# Controller_v1.net
KiCad netlist of a schematic drawn in EAGLE
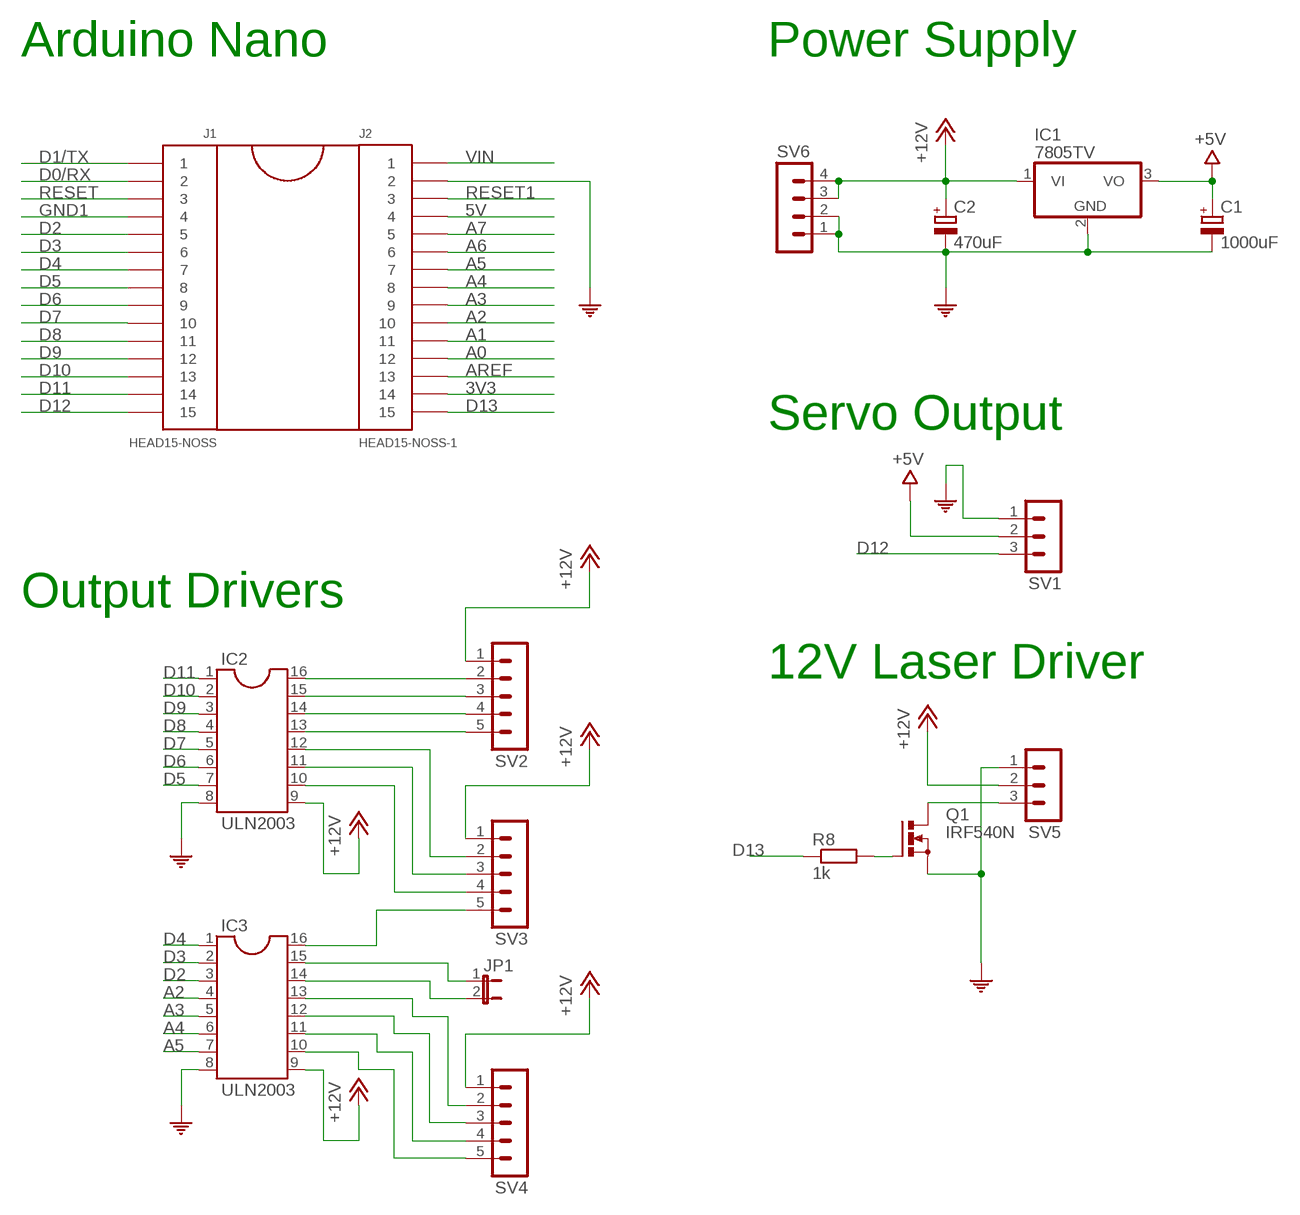
[diagram p0: schematic, sheet 1]

(export (version "E")
  (design (tool "Eeschema 10.0.6"))
  (components
    (comp (ref "C1")
      (value "1000uF")
      (footprint "eagle-import:TAP5-70")
      (libsource (lib "eagle-import") (part "CPOL-EUTAP5-70"))
    )
    (comp (ref "C2")
      (value "470uF")
      (footprint "eagle-import:TAP5-70")
      (libsource (lib "eagle-import") (part "CPOL-EUTAP5-70"))
    )
    (comp (ref "IC1")
      (value "7805TV")
      (footprint "eagle-import:TO220V")
      (libsource (lib "eagle-import") (part "78TV05"))
    )
    (comp (ref "IC2")
      (value "ULN2003")
      (footprint "eagle-import:DIL16")
      (libsource (lib "eagle-import") (part "DIL16"))
    )
    (comp (ref "IC3")
      (value "ULN2003")
      (footprint "eagle-import:DIL16")
      (libsource (lib "eagle-import") (part "DIL16"))
    )
    (comp (ref "J1")
      (value "HEAD15-NOSS")
      (footprint "eagle-import:HEAD15-NOSS")
      (libsource (lib "eagle-import") (part "HEAD15-NOSS"))
    )
    (comp (ref "J2")
      (value "HEAD15-NOSS-1")
      (footprint "eagle-import:HEAD15-NOSS-1")
      (libsource (lib "eagle-import") (part "HEAD15-NOSS-1"))
    )
    (comp (ref "JP1")
      (value "JP1E")
      (footprint "eagle-import:JP1")
      (libsource (lib "eagle-import") (part "JP1E"))
    )
    (comp (ref "Q1")
      (value "IRF540N")
      (footprint "eagle-import:TO220BV")
      (libsource (lib "eagle-import") (part "PMOSFET_NTO220BV"))
    )
    (comp (ref "R8")
      (value "1k")
      (footprint "eagle-import:0207_10")
      (libsource (lib "eagle-import") (part "R-EU_0207/10"))
    )
    (comp (ref "SV1")
      (value "MA03-1")
      (footprint "eagle-import:MA03-1")
      (libsource (lib "eagle-import") (part "MA03-1"))
    )
    (comp (ref "SV2")
      (value "MA05-1")
      (footprint "eagle-import:MA05-1")
      (libsource (lib "eagle-import") (part "MA05-1"))
    )
    (comp (ref "SV3")
      (value "MA05-1")
      (footprint "eagle-import:MA05-1")
      (libsource (lib "eagle-import") (part "MA05-1"))
    )
    (comp (ref "SV4")
      (value "MA05-1")
      (footprint "eagle-import:MA05-1")
      (libsource (lib "eagle-import") (part "MA05-1"))
    )
    (comp (ref "SV5")
      (value "MA03-1")
      (footprint "eagle-import:MA03-1")
      (libsource (lib "eagle-import") (part "MA03-1"))
    )
    (comp (ref "SV6")
      (value "MA04-1")
      (footprint "eagle-import:MA04-1")
      (libsource (lib "eagle-import") (part "MA04-1"))
    )
  )
  (nets
    (net (code "1") (name "+5V") (class "Default")
      (node (ref "C1") (pin "+") (pinfunction "+_+") (pintype "passive"))
      (node (ref "IC1") (pin "3") (pinfunction "VO_3") (pintype "passive"))
      (node (ref "SV1") (pin "2") (pinfunction "2_2") (pintype "passive"))
    )
    (net (code "2") (name "+12V") (class "Default")
      (node (ref "C2") (pin "+") (pinfunction "+_+") (pintype "passive"))
      (node (ref "IC1") (pin "1") (pinfunction "VI_1") (pintype "input"))
      (node (ref "IC2") (pin "9") (pinfunction "9_9") (pintype "passive"))
      (node (ref "IC3") (pin "9") (pinfunction "9_9") (pintype "passive"))
      (node (ref "SV2") (pin "1") (pinfunction "1_1") (pintype "passive"))
      (node (ref "SV3") (pin "1") (pinfunction "1_1") (pintype "passive"))
      (node (ref "SV4") (pin "1") (pinfunction "1_1") (pintype "passive"))
      (node (ref "SV5") (pin "2") (pinfunction "2_2") (pintype "passive"))
      (node (ref "SV6") (pin "3") (pinfunction "3_3") (pintype "passive"))
      (node (ref "SV6") (pin "4") (pinfunction "4_4") (pintype "passive"))
    )
    (net (code "3") (name "/3V3") (class "Default")
      (node (ref "J2") (pin "14") (pinfunction "14_14") (pintype "passive"))
    )
    (net (code "4") (name "/5V") (class "Default")
      (node (ref "J2") (pin "4") (pinfunction "4_4") (pintype "passive"))
    )
    (net (code "5") (name "/A0") (class "Default")
      (node (ref "J2") (pin "12") (pinfunction "12_12") (pintype "passive"))
    )
    (net (code "6") (name "/A1") (class "Default")
      (node (ref "J2") (pin "11") (pinfunction "11_11") (pintype "passive"))
    )
    (net (code "7") (name "/A2") (class "Default")
      (node (ref "IC3") (pin "4") (pinfunction "4_4") (pintype "passive"))
      (node (ref "J2") (pin "10") (pinfunction "10_10") (pintype "passive"))
    )
    (net (code "8") (name "/A3") (class "Default")
      (node (ref "IC3") (pin "5") (pinfunction "5_5") (pintype "passive"))
      (node (ref "J2") (pin "9") (pinfunction "9_9") (pintype "passive"))
    )
    (net (code "9") (name "/A4") (class "Default")
      (node (ref "IC3") (pin "6") (pinfunction "6_6") (pintype "passive"))
      (node (ref "J2") (pin "8") (pinfunction "8_8") (pintype "passive"))
    )
    (net (code "10") (name "/A5") (class "Default")
      (node (ref "IC3") (pin "7") (pinfunction "7_7") (pintype "passive"))
      (node (ref "J2") (pin "7") (pinfunction "7_7") (pintype "passive"))
    )
    (net (code "11") (name "/A6") (class "Default")
      (node (ref "J2") (pin "6") (pinfunction "6_6") (pintype "passive"))
    )
    (net (code "12") (name "/A7") (class "Default")
      (node (ref "J2") (pin "5") (pinfunction "5_5") (pintype "passive"))
    )
    (net (code "13") (name "/AREF") (class "Default")
      (node (ref "J2") (pin "13") (pinfunction "13_13") (pintype "passive"))
    )
    (net (code "14") (name "/D0{slash}RX") (class "Default")
      (node (ref "J1") (pin "2") (pinfunction "2_2") (pintype "passive"))
    )
    (net (code "15") (name "/D1{slash}TX") (class "Default")
      (node (ref "J1") (pin "1") (pinfunction "1_1") (pintype "passive"))
    )
    (net (code "16") (name "/D2") (class "Default")
      (node (ref "IC3") (pin "3") (pinfunction "3_3") (pintype "passive"))
      (node (ref "J1") (pin "5") (pinfunction "5_5") (pintype "passive"))
    )
    (net (code "17") (name "/D3") (class "Default")
      (node (ref "IC3") (pin "2") (pinfunction "2_2") (pintype "passive"))
      (node (ref "J1") (pin "6") (pinfunction "6_6") (pintype "passive"))
    )
    (net (code "18") (name "/D4") (class "Default")
      (node (ref "IC3") (pin "1") (pinfunction "1_1") (pintype "passive"))
      (node (ref "J1") (pin "7") (pinfunction "7_7") (pintype "passive"))
    )
    (net (code "19") (name "/D5") (class "Default")
      (node (ref "IC2") (pin "7") (pinfunction "7_7") (pintype "passive"))
      (node (ref "J1") (pin "8") (pinfunction "8_8") (pintype "passive"))
    )
    (net (code "20") (name "/D6") (class "Default")
      (node (ref "IC2") (pin "6") (pinfunction "6_6") (pintype "passive"))
      (node (ref "J1") (pin "9") (pinfunction "9_9") (pintype "passive"))
    )
    (net (code "21") (name "/D7") (class "Default")
      (node (ref "IC2") (pin "5") (pinfunction "5_5") (pintype "passive"))
      (node (ref "J1") (pin "10") (pinfunction "10_10") (pintype "passive"))
    )
    (net (code "22") (name "/D8") (class "Default")
      (node (ref "IC2") (pin "4") (pinfunction "4_4") (pintype "passive"))
      (node (ref "J1") (pin "11") (pinfunction "11_11") (pintype "passive"))
    )
    (net (code "23") (name "/D9") (class "Default")
      (node (ref "IC2") (pin "3") (pinfunction "3_3") (pintype "passive"))
      (node (ref "J1") (pin "12") (pinfunction "12_12") (pintype "passive"))
    )
    (net (code "24") (name "/D10") (class "Default")
      (node (ref "IC2") (pin "2") (pinfunction "2_2") (pintype "passive"))
      (node (ref "J1") (pin "13") (pinfunction "13_13") (pintype "passive"))
    )
    (net (code "25") (name "/D11") (class "Default")
      (node (ref "IC2") (pin "1") (pinfunction "1_1") (pintype "passive"))
      (node (ref "J1") (pin "14") (pinfunction "14_14") (pintype "passive"))
    )
    (net (code "26") (name "/D12") (class "Default")
      (node (ref "J1") (pin "15") (pinfunction "15_15") (pintype "passive"))
      (node (ref "SV1") (pin "3") (pinfunction "3_3") (pintype "passive"))
    )
    (net (code "27") (name "/D13") (class "Default")
      (node (ref "J2") (pin "15") (pinfunction "15_15") (pintype "passive"))
      (node (ref "R8") (pin "1") (pinfunction "1_1") (pintype "passive"))
    )
    (net (code "28") (name "/GND1") (class "Default")
      (node (ref "J1") (pin "4") (pinfunction "4_4") (pintype "passive"))
    )
    (net (code "29") (name "/RESET") (class "Default")
      (node (ref "J1") (pin "3") (pinfunction "3_3") (pintype "passive"))
    )
    (net (code "30") (name "/RESET1") (class "Default")
      (node (ref "J2") (pin "3") (pinfunction "3_3") (pintype "passive"))
    )
    (net (code "31") (name "/VIN") (class "Default")
      (node (ref "J2") (pin "1") (pinfunction "1_1") (pintype "passive"))
    )
    (net (code "32") (name "COM") (class "Default")
      (node (ref "C1") (pin "-") (pinfunction "-_-") (pintype "passive"))
      (node (ref "C2") (pin "-") (pinfunction "-_-") (pintype "passive"))
      (node (ref "IC1") (pin "2") (pinfunction "GND_2") (pintype "passive"))
      (node (ref "IC2") (pin "8") (pinfunction "8_8") (pintype "passive"))
      (node (ref "IC3") (pin "8") (pinfunction "8_8") (pintype "passive"))
      (node (ref "J2") (pin "2") (pinfunction "2_2") (pintype "passive"))
      (node (ref "Q1") (pin "S") (pinfunction "S_S") (pintype "passive"))
      (node (ref "SV1") (pin "1") (pinfunction "1_1") (pintype "passive"))
      (node (ref "SV5") (pin "1") (pinfunction "1_1") (pintype "passive"))
      (node (ref "SV6") (pin "1") (pinfunction "1_1") (pintype "passive"))
      (node (ref "SV6") (pin "2") (pinfunction "2_2") (pintype "passive"))
    )
    (net (code "33") (name "Net-(IC2-Pad10)") (class "Default")
      (node (ref "IC2") (pin "10") (pinfunction "10_10") (pintype "passive"))
      (node (ref "SV3") (pin "4") (pinfunction "4_4") (pintype "passive"))
    )
    (net (code "34") (name "Net-(IC2-Pad11)") (class "Default")
      (node (ref "IC2") (pin "11") (pinfunction "11_11") (pintype "passive"))
      (node (ref "SV3") (pin "3") (pinfunction "3_3") (pintype "passive"))
    )
    (net (code "35") (name "Net-(IC2-Pad12)") (class "Default")
      (node (ref "IC2") (pin "12") (pinfunction "12_12") (pintype "passive"))
      (node (ref "SV3") (pin "2") (pinfunction "2_2") (pintype "passive"))
    )
    (net (code "36") (name "Net-(IC2-Pad13)") (class "Default")
      (node (ref "IC2") (pin "13") (pinfunction "13_13") (pintype "passive"))
      (node (ref "SV2") (pin "5") (pinfunction "5_5") (pintype "passive"))
    )
    (net (code "37") (name "Net-(IC2-Pad14)") (class "Default")
      (node (ref "IC2") (pin "14") (pinfunction "14_14") (pintype "passive"))
      (node (ref "SV2") (pin "4") (pinfunction "4_4") (pintype "passive"))
    )
    (net (code "38") (name "Net-(IC2-Pad15)") (class "Default")
      (node (ref "IC2") (pin "15") (pinfunction "15_15") (pintype "passive"))
      (node (ref "SV2") (pin "3") (pinfunction "3_3") (pintype "passive"))
    )
    (net (code "39") (name "Net-(IC2-Pad16)") (class "Default")
      (node (ref "IC2") (pin "16") (pinfunction "16_16") (pintype "passive"))
      (node (ref "SV2") (pin "2") (pinfunction "2_2") (pintype "passive"))
    )
    (net (code "40") (name "Net-(IC3-Pad10)") (class "Default")
      (node (ref "IC3") (pin "10") (pinfunction "10_10") (pintype "passive"))
      (node (ref "SV4") (pin "5") (pinfunction "5_5") (pintype "passive"))
    )
    (net (code "41") (name "Net-(IC3-Pad11)") (class "Default")
      (node (ref "IC3") (pin "11") (pinfunction "11_11") (pintype "passive"))
      (node (ref "SV4") (pin "4") (pinfunction "4_4") (pintype "passive"))
    )
    (net (code "42") (name "Net-(IC3-Pad12)") (class "Default")
      (node (ref "IC3") (pin "12") (pinfunction "12_12") (pintype "passive"))
      (node (ref "SV4") (pin "3") (pinfunction "3_3") (pintype "passive"))
    )
    (net (code "43") (name "Net-(IC3-Pad13)") (class "Default")
      (node (ref "IC3") (pin "13") (pinfunction "13_13") (pintype "passive"))
      (node (ref "SV4") (pin "2") (pinfunction "2_2") (pintype "passive"))
    )
    (net (code "44") (name "Net-(IC3-Pad14)") (class "Default")
      (node (ref "IC3") (pin "14") (pinfunction "14_14") (pintype "passive"))
      (node (ref "JP1") (pin "2") (pinfunction "2_2") (pintype "passive"))
    )
    (net (code "45") (name "Net-(IC3-Pad15)") (class "Default")
      (node (ref "IC3") (pin "15") (pinfunction "15_15") (pintype "passive"))
      (node (ref "JP1") (pin "1") (pinfunction "1_1") (pintype "passive"))
    )
    (net (code "46") (name "Net-(IC3-Pad16)") (class "Default")
      (node (ref "IC3") (pin "16") (pinfunction "16_16") (pintype "passive"))
      (node (ref "SV3") (pin "5") (pinfunction "5_5") (pintype "passive"))
    )
    (net (code "47") (name "Net-(Q1-PadD)") (class "Default")
      (node (ref "Q1") (pin "D") (pinfunction "D_D") (pintype "passive"))
      (node (ref "SV5") (pin "3") (pinfunction "3_3") (pintype "passive"))
    )
    (net (code "48") (name "Net-(Q1-PadG)") (class "Default")
      (node (ref "Q1") (pin "G") (pinfunction "G_G") (pintype "passive"))
      (node (ref "R8") (pin "2") (pinfunction "2_2") (pintype "passive"))
    )
  )
)
